# TSOC_Block_Template_Dual_SMD.net
KiCad netlist of a schematic drawn in EAGLE
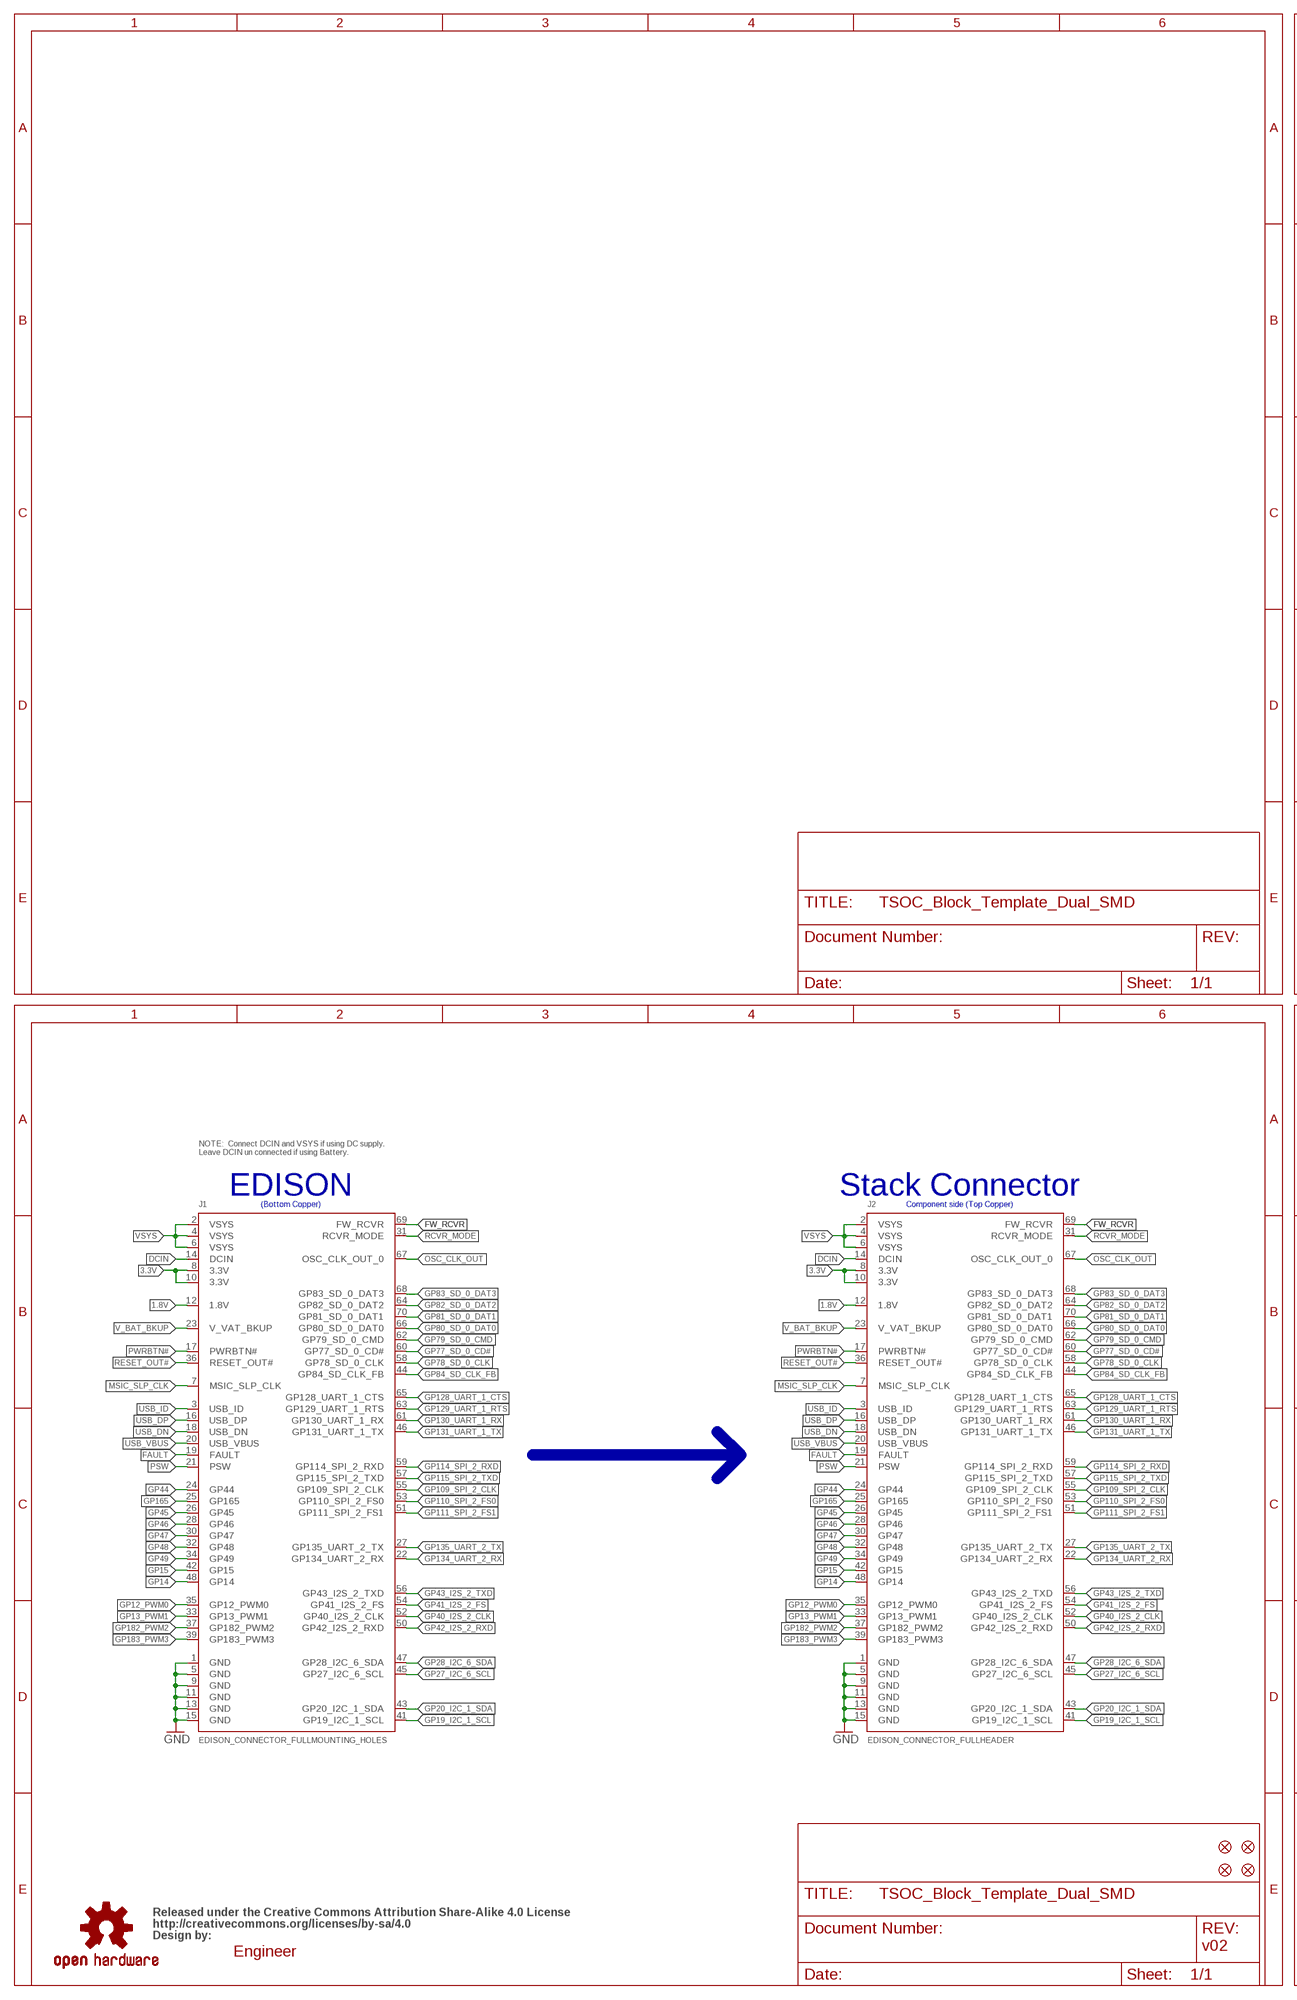
[diagram p0: schematic, sheet 1, part 1 of 2]
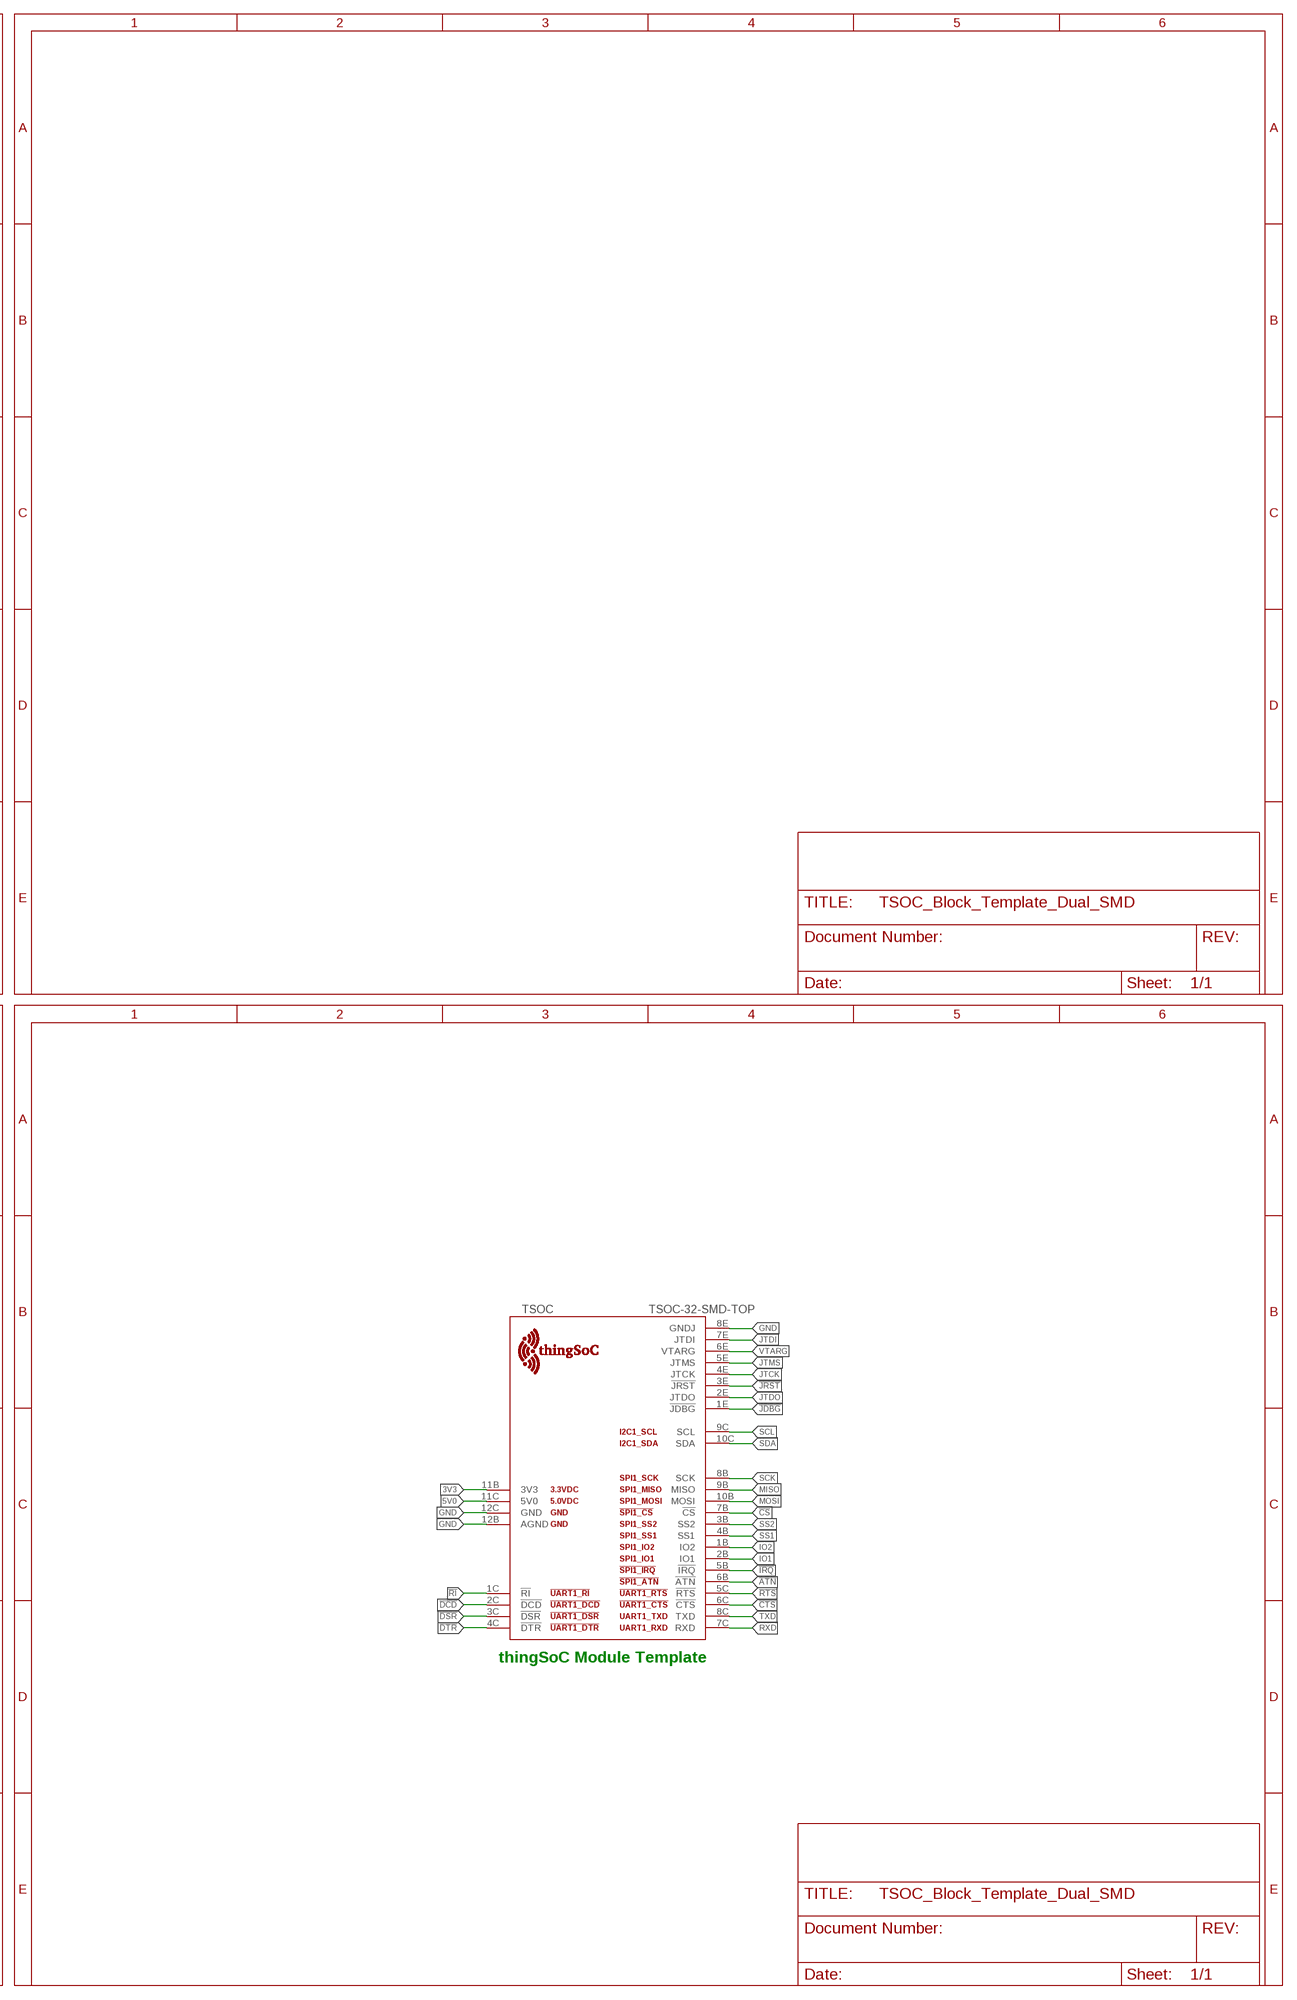
[diagram p1: schematic, sheet 1, part 2 of 2]

(export (version "E")
  (design (tool "Eeschema 10.0.6"))
  (components
    (comp (ref "FID5")
      (value "FIDUCIAL1X2")
      (footprint "eagle-import:FIDUCIAL-1X2")
      (libsource (lib "eagle-import") (part "FIDUCIAL1X2"))
    )
    (comp (ref "FID6")
      (value "FIDUCIAL1X2")
      (footprint "eagle-import:FIDUCIAL-1X2")
      (libsource (lib "eagle-import") (part "FIDUCIAL1X2"))
    )
    (comp (ref "FID7")
      (value "FIDUCIAL1X2")
      (footprint "eagle-import:FIDUCIAL-1X2")
      (libsource (lib "eagle-import") (part "FIDUCIAL1X2"))
    )
    (comp (ref "FID8")
      (value "FIDUCIAL1X2")
      (footprint "eagle-import:FIDUCIAL-1X2")
      (libsource (lib "eagle-import") (part "FIDUCIAL1X2"))
    )
    (comp (ref "J1")
      (value "EDISON_CONNECTOR_FULLMOUNTING_HOLES")
      (footprint "eagle-import:EDISON_DAUGHTER")
      (libsource (lib "eagle-import") (part "EDISON_CONNECTOR_FULLMOUNTING_HOLES"))
    )
    (comp (ref "J2")
      (value "EDISON_CONNECTOR_FULLHEADER")
      (footprint "eagle-import:DF40C-70DP-0.4(51)")
      (libsource (lib "eagle-import") (part "EDISON_CONNECTOR_FULLHEADER"))
    )
    (comp (ref "LOGO5")
      (value "OSHW-LOGOS")
      (footprint "eagle-import:OSHW-LOGO-S")
      (libsource (lib "eagle-import") (part "OSHW-LOGOS"))
    )
    (comp (ref "TSOC")
      (value "TSOC-32-SMD-TOP")
      (footprint "eagle-import:TSOC-BB-S32-SMD-TOP")
      (libsource (lib "eagle-import") (part "TSOC-32-SMD-TOP"))
    )
    (comp (ref "U$1")
      (value "BY_CC_SA_TEXTTEXT")
      (footprint "eagle-import:BY_CC_SA_TEXT")
      (libsource (lib "eagle-import") (part "BY_CC_SA_TEXTTEXT"))
    )
  )
  (nets
    (net (code "1") (name "/~{ATN}") (class "Default")
      (node (ref "TSOC") (pin "6B") (pinfunction "~{ATN}_6B") (pintype "bidirectional"))
    )
    (net (code "2") (name "/~{CS}") (class "Default")
      (node (ref "TSOC") (pin "7B") (pinfunction "~{CS}_7B") (pintype "bidirectional"))
    )
    (net (code "3") (name "/~{CTS}") (class "Default")
      (node (ref "TSOC") (pin "6C") (pinfunction "~{CTS}_6C") (pintype "bidirectional"))
    )
    (net (code "4") (name "/~{DCD}") (class "Default")
      (node (ref "TSOC") (pin "2C") (pinfunction "~{DCD}_2C") (pintype "bidirectional"))
    )
    (net (code "5") (name "/~{DSR}") (class "Default")
      (node (ref "TSOC") (pin "3C") (pinfunction "~{DSR}_3C") (pintype "bidirectional"))
    )
    (net (code "6") (name "/~{DTR}") (class "Default")
      (node (ref "TSOC") (pin "4C") (pinfunction "~{DTR}_4C") (pintype "bidirectional"))
    )
    (net (code "7") (name "/~{IRQ}") (class "Default")
      (node (ref "TSOC") (pin "5B") (pinfunction "~{IRQ}_5B") (pintype "bidirectional"))
    )
    (net (code "8") (name "/~{JDBG}") (class "Default")
      (node (ref "TSOC") (pin "1E") (pinfunction "~{JDBG}_1E") (pintype "bidirectional"))
    )
    (net (code "9") (name "/~{JRST}") (class "Default")
      (node (ref "TSOC") (pin "3E") (pinfunction "~{JRST}_3E") (pintype "bidirectional"))
    )
    (net (code "10") (name "/~{RI}") (class "Default")
      (node (ref "TSOC") (pin "1C") (pinfunction "~{RI}_1C") (pintype "bidirectional"))
    )
    (net (code "11") (name "/~{RTS}") (class "Default")
      (node (ref "TSOC") (pin "5C") (pinfunction "~{RTS}_5C") (pintype "bidirectional"))
    )
    (net (code "12") (name "1.8V") (class "Default")
      (node (ref "J1") (pin "12") (pinfunction "1.8V_12") (pintype "bidirectional"))
      (node (ref "J2") (pin "12") (pinfunction "1.8V_12") (pintype "bidirectional"))
    )
    (net (code "13") (name "3.3V") (class "Default")
      (node (ref "J1") (pin "10") (pinfunction "3.3V_10") (pintype "bidirectional"))
      (node (ref "J1") (pin "8") (pinfunction "3.3V_8") (pintype "bidirectional"))
      (node (ref "J2") (pin "10") (pinfunction "3.3V_10") (pintype "bidirectional"))
      (node (ref "J2") (pin "8") (pinfunction "3.3V_8") (pintype "bidirectional"))
    )
    (net (code "14") (name "3V3") (class "Default")
      (node (ref "TSOC") (pin "11B") (pinfunction "3V3_11B") (pintype "bidirectional"))
    )
    (net (code "15") (name "5V0") (class "Default")
      (node (ref "TSOC") (pin "11C") (pinfunction "5V0_11C") (pintype "bidirectional"))
    )
    (net (code "16") (name "DCIN") (class "Default")
      (node (ref "J1") (pin "14") (pinfunction "DCIN_14") (pintype "bidirectional"))
      (node (ref "J2") (pin "14") (pinfunction "DCIN_14") (pintype "bidirectional"))
    )
    (net (code "17") (name "FAULT") (class "Default")
      (node (ref "J1") (pin "19") (pinfunction "FAULT_19") (pintype "bidirectional"))
      (node (ref "J2") (pin "19") (pinfunction "FAULT_19") (pintype "bidirectional"))
    )
    (net (code "18") (name "FW_RCVR") (class "Default")
      (node (ref "J1") (pin "69") (pinfunction "FW_RCVR_69") (pintype "bidirectional"))
      (node (ref "J2") (pin "69") (pinfunction "FW_RCVR_69") (pintype "bidirectional"))
    )
    (net (code "19") (name "GND") (class "Default")
      (node (ref "J1") (pin "1") (pinfunction "GND_1") (pintype "bidirectional"))
      (node (ref "J1") (pin "11") (pinfunction "GND_11") (pintype "bidirectional"))
      (node (ref "J1") (pin "13") (pinfunction "GND_13") (pintype "bidirectional"))
      (node (ref "J1") (pin "15") (pinfunction "GND_15") (pintype "bidirectional"))
      (node (ref "J1") (pin "5") (pinfunction "GND_5") (pintype "bidirectional"))
      (node (ref "J1") (pin "9") (pinfunction "GND_9") (pintype "bidirectional"))
      (node (ref "J2") (pin "1") (pinfunction "GND_1") (pintype "bidirectional"))
      (node (ref "J2") (pin "11") (pinfunction "GND_11") (pintype "bidirectional"))
      (node (ref "J2") (pin "13") (pinfunction "GND_13") (pintype "bidirectional"))
      (node (ref "J2") (pin "15") (pinfunction "GND_15") (pintype "bidirectional"))
      (node (ref "J2") (pin "5") (pinfunction "GND_5") (pintype "bidirectional"))
      (node (ref "J2") (pin "9") (pinfunction "GND_9") (pintype "bidirectional"))
      (node (ref "TSOC") (pin "12B") (pinfunction "AGND_12B") (pintype "bidirectional"))
      (node (ref "TSOC") (pin "12C") (pinfunction "GND_12C") (pintype "bidirectional"))
      (node (ref "TSOC") (pin "8E") (pinfunction "GNDJ_8E") (pintype "bidirectional"))
    )
    (net (code "20") (name "GP12_PWM0") (class "Default")
      (node (ref "J1") (pin "35") (pinfunction "GP12_PWM0_35") (pintype "bidirectional"))
      (node (ref "J2") (pin "35") (pinfunction "GP12_PWM0_35") (pintype "bidirectional"))
    )
    (net (code "21") (name "GP13_PWM1") (class "Default")
      (node (ref "J1") (pin "33") (pinfunction "GP13_PWM1_33") (pintype "bidirectional"))
      (node (ref "J2") (pin "33") (pinfunction "GP13_PWM1_33") (pintype "bidirectional"))
    )
    (net (code "22") (name "GP14") (class "Default")
      (node (ref "J1") (pin "48") (pinfunction "GP14_48") (pintype "bidirectional"))
      (node (ref "J2") (pin "48") (pinfunction "GP14_48") (pintype "bidirectional"))
    )
    (net (code "23") (name "GP15") (class "Default")
      (node (ref "J1") (pin "42") (pinfunction "GP15_42") (pintype "bidirectional"))
      (node (ref "J2") (pin "42") (pinfunction "GP15_42") (pintype "bidirectional"))
    )
    (net (code "24") (name "GP19_I2C_1_SCL") (class "Default")
      (node (ref "J1") (pin "41") (pinfunction "GP19_I2C_1_SCL_41") (pintype "bidirectional"))
      (node (ref "J2") (pin "41") (pinfunction "GP19_I2C_1_SCL_41") (pintype "bidirectional"))
    )
    (net (code "25") (name "GP20_I2C_1_SDA") (class "Default")
      (node (ref "J1") (pin "43") (pinfunction "GP20_I2C_1_SDA_43") (pintype "bidirectional"))
      (node (ref "J2") (pin "43") (pinfunction "GP20_I2C_1_SDA_43") (pintype "bidirectional"))
    )
    (net (code "26") (name "GP27_I2C_6_SCL") (class "Default")
      (node (ref "J1") (pin "45") (pinfunction "GP27_I2C_6_SCL_45") (pintype "bidirectional"))
      (node (ref "J2") (pin "45") (pinfunction "GP27_I2C_6_SCL_45") (pintype "bidirectional"))
    )
    (net (code "27") (name "GP28_I2C_6_SDA") (class "Default")
      (node (ref "J1") (pin "47") (pinfunction "GP28_I2C_6_SDA_47") (pintype "bidirectional"))
      (node (ref "J2") (pin "47") (pinfunction "GP28_I2C_6_SDA_47") (pintype "bidirectional"))
    )
    (net (code "28") (name "GP40_I2S_2_CLK") (class "Default")
      (node (ref "J1") (pin "52") (pinfunction "GP40_I2S_2_CLK_52") (pintype "bidirectional"))
      (node (ref "J2") (pin "52") (pinfunction "GP40_I2S_2_CLK_52") (pintype "bidirectional"))
    )
    (net (code "29") (name "GP41_I2S_2_FS") (class "Default")
      (node (ref "J1") (pin "54") (pinfunction "GP41_I2S_2_FS_54") (pintype "bidirectional"))
      (node (ref "J2") (pin "54") (pinfunction "GP41_I2S_2_FS_54") (pintype "bidirectional"))
    )
    (net (code "30") (name "GP42_I2S_2_RXD") (class "Default")
      (node (ref "J1") (pin "50") (pinfunction "GP42_I2S_2_RXD_50") (pintype "bidirectional"))
      (node (ref "J2") (pin "50") (pinfunction "GP42_I2S_2_RXD_50") (pintype "bidirectional"))
    )
    (net (code "31") (name "GP43_I2S_2_TXD") (class "Default")
      (node (ref "J1") (pin "56") (pinfunction "GP43_I2S_2_TXD_56") (pintype "bidirectional"))
      (node (ref "J2") (pin "56") (pinfunction "GP43_I2S_2_TXD_56") (pintype "bidirectional"))
    )
    (net (code "32") (name "GP44") (class "Default")
      (node (ref "J1") (pin "24") (pinfunction "GP44_24") (pintype "bidirectional"))
      (node (ref "J2") (pin "24") (pinfunction "GP44_24") (pintype "bidirectional"))
    )
    (net (code "33") (name "GP45") (class "Default")
      (node (ref "J1") (pin "26") (pinfunction "GP45_26") (pintype "bidirectional"))
      (node (ref "J2") (pin "26") (pinfunction "GP45_26") (pintype "bidirectional"))
    )
    (net (code "34") (name "GP46") (class "Default")
      (node (ref "J1") (pin "28") (pinfunction "GP46_28") (pintype "bidirectional"))
      (node (ref "J2") (pin "28") (pinfunction "GP46_28") (pintype "bidirectional"))
    )
    (net (code "35") (name "GP47") (class "Default")
      (node (ref "J1") (pin "30") (pinfunction "GP47_30") (pintype "bidirectional"))
      (node (ref "J2") (pin "30") (pinfunction "GP47_30") (pintype "bidirectional"))
    )
    (net (code "36") (name "GP48") (class "Default")
      (node (ref "J1") (pin "32") (pinfunction "GP48_32") (pintype "bidirectional"))
      (node (ref "J2") (pin "32") (pinfunction "GP48_32") (pintype "bidirectional"))
    )
    (net (code "37") (name "GP49") (class "Default")
      (node (ref "J1") (pin "34") (pinfunction "GP49_34") (pintype "bidirectional"))
      (node (ref "J2") (pin "34") (pinfunction "GP49_34") (pintype "bidirectional"))
    )
    (net (code "38") (name "GP77_SD_0_CD#") (class "Default")
      (node (ref "J1") (pin "60") (pinfunction "GP77_SD_0_CD#_60") (pintype "bidirectional"))
      (node (ref "J2") (pin "60") (pinfunction "GP77_SD_0_CD#_60") (pintype "bidirectional"))
    )
    (net (code "39") (name "GP78_SD_0_CLK") (class "Default")
      (node (ref "J1") (pin "58") (pinfunction "GP78_SD_0_CLK_58") (pintype "bidirectional"))
      (node (ref "J2") (pin "58") (pinfunction "GP78_SD_0_CLK_58") (pintype "bidirectional"))
    )
    (net (code "40") (name "GP79_SD_0_CMD") (class "Default")
      (node (ref "J1") (pin "62") (pinfunction "GP79_SD_0_CMD_62") (pintype "bidirectional"))
      (node (ref "J2") (pin "62") (pinfunction "GP79_SD_0_CMD_62") (pintype "bidirectional"))
    )
    (net (code "41") (name "GP80_SD_0_DAT0") (class "Default")
      (node (ref "J1") (pin "66") (pinfunction "GP80_SD_0_DAT0_66") (pintype "bidirectional"))
      (node (ref "J2") (pin "66") (pinfunction "GP80_SD_0_DAT0_66") (pintype "bidirectional"))
    )
    (net (code "42") (name "GP81_SD_0_DAT1") (class "Default")
      (node (ref "J1") (pin "70") (pinfunction "GP81_SD_0_DAT1_70") (pintype "bidirectional"))
      (node (ref "J2") (pin "70") (pinfunction "GP81_SD_0_DAT1_70") (pintype "bidirectional"))
    )
    (net (code "43") (name "GP82_SD_0_DAT2") (class "Default")
      (node (ref "J1") (pin "64") (pinfunction "GP82_SD_0_DAT2_64") (pintype "bidirectional"))
      (node (ref "J2") (pin "64") (pinfunction "GP82_SD_0_DAT2_64") (pintype "bidirectional"))
    )
    (net (code "44") (name "GP83_SD_0_DAT3") (class "Default")
      (node (ref "J1") (pin "68") (pinfunction "GP83_SD_0_DAT3_68") (pintype "bidirectional"))
      (node (ref "J2") (pin "68") (pinfunction "GP83_SD_0_DAT3_68") (pintype "bidirectional"))
    )
    (net (code "45") (name "GP84_SD_CLK_FB") (class "Default")
      (node (ref "J1") (pin "44") (pinfunction "GP84_SD_CLK_FB_44") (pintype "bidirectional"))
      (node (ref "J2") (pin "44") (pinfunction "GP84_SD_CLK_FB_44") (pintype "bidirectional"))
    )
    (net (code "46") (name "GP109_SPI_2_CLK") (class "Default")
      (node (ref "J1") (pin "55") (pinfunction "GP109_SPI_2_CLK_55") (pintype "bidirectional"))
      (node (ref "J2") (pin "55") (pinfunction "GP109_SPI_2_CLK_55") (pintype "bidirectional"))
    )
    (net (code "47") (name "GP110_SPI_2_FS0") (class "Default")
      (node (ref "J1") (pin "53") (pinfunction "GP110_SPI_2_FS0_53") (pintype "bidirectional"))
      (node (ref "J2") (pin "53") (pinfunction "GP110_SPI_2_FS0_53") (pintype "bidirectional"))
    )
    (net (code "48") (name "GP111_SPI_2_FS1") (class "Default")
      (node (ref "J1") (pin "51") (pinfunction "GP111_SPI_2_FS1_51") (pintype "bidirectional"))
      (node (ref "J2") (pin "51") (pinfunction "GP111_SPI_2_FS1_51") (pintype "bidirectional"))
    )
    (net (code "49") (name "GP114_SPI_2_RXD") (class "Default")
      (node (ref "J1") (pin "59") (pinfunction "GP114_SPI_2_RXD_59") (pintype "bidirectional"))
      (node (ref "J2") (pin "59") (pinfunction "GP114_SPI_2_RXD_59") (pintype "bidirectional"))
    )
    (net (code "50") (name "GP115_SPI_2_TXD") (class "Default")
      (node (ref "J1") (pin "57") (pinfunction "GP115_SPI_2_TXD_57") (pintype "bidirectional"))
      (node (ref "J2") (pin "57") (pinfunction "GP115_SPI_2_TXD_57") (pintype "bidirectional"))
    )
    (net (code "51") (name "GP128_UART_1_CTS") (class "Default")
      (node (ref "J1") (pin "65") (pinfunction "GP128_UART_1_CTS_65") (pintype "bidirectional"))
      (node (ref "J2") (pin "65") (pinfunction "GP128_UART_1_CTS_65") (pintype "bidirectional"))
    )
    (net (code "52") (name "GP129_UART_1_RTS") (class "Default")
      (node (ref "J1") (pin "63") (pinfunction "GP129_UART_1_RTS_63") (pintype "bidirectional"))
      (node (ref "J2") (pin "63") (pinfunction "GP129_UART_1_RTS_63") (pintype "bidirectional"))
    )
    (net (code "53") (name "GP130_UART_1_RX") (class "Default")
      (node (ref "J1") (pin "61") (pinfunction "GP130_UART_1_RX_61") (pintype "bidirectional"))
      (node (ref "J2") (pin "61") (pinfunction "GP130_UART_1_RX_61") (pintype "bidirectional"))
    )
    (net (code "54") (name "GP131_UART_1_TX") (class "Default")
      (node (ref "J1") (pin "46") (pinfunction "GP131_UART_1_TX_46") (pintype "bidirectional"))
      (node (ref "J2") (pin "46") (pinfunction "GP131_UART_1_TX_46") (pintype "bidirectional"))
    )
    (net (code "55") (name "GP134_UART_2_RX") (class "Default")
      (node (ref "J1") (pin "22") (pinfunction "GP134_UART_2_RX_22") (pintype "bidirectional"))
      (node (ref "J2") (pin "22") (pinfunction "GP134_UART_2_RX_22") (pintype "bidirectional"))
    )
    (net (code "56") (name "GP135_UART_2_TX") (class "Default")
      (node (ref "J1") (pin "27") (pinfunction "GP135_UART_2_TX_27") (pintype "bidirectional"))
      (node (ref "J2") (pin "27") (pinfunction "GP135_UART_2_TX_27") (pintype "bidirectional"))
    )
    (net (code "57") (name "GP165") (class "Default")
      (node (ref "J1") (pin "25") (pinfunction "GP165_25") (pintype "bidirectional"))
      (node (ref "J2") (pin "25") (pinfunction "GP165_25") (pintype "bidirectional"))
    )
    (net (code "58") (name "GP182_PWM2") (class "Default")
      (node (ref "J1") (pin "37") (pinfunction "GP182_PWM2_37") (pintype "bidirectional"))
      (node (ref "J2") (pin "37") (pinfunction "GP182_PWM2_37") (pintype "bidirectional"))
    )
    (net (code "59") (name "GP183_PWM3") (class "Default")
      (node (ref "J1") (pin "39") (pinfunction "GP183_PWM3_39") (pintype "bidirectional"))
      (node (ref "J2") (pin "39") (pinfunction "GP183_PWM3_39") (pintype "bidirectional"))
    )
    (net (code "60") (name "IO1") (class "Default")
      (node (ref "TSOC") (pin "2B") (pinfunction "IO1_2B") (pintype "bidirectional"))
    )
    (net (code "61") (name "IO2") (class "Default")
      (node (ref "TSOC") (pin "1B") (pinfunction "IO2_1B") (pintype "bidirectional"))
    )
    (net (code "62") (name "JTCK") (class "Default")
      (node (ref "TSOC") (pin "4E") (pinfunction "JTCK_4E") (pintype "bidirectional"))
    )
    (net (code "63") (name "JTDI") (class "Default")
      (node (ref "TSOC") (pin "7E") (pinfunction "JTDI_7E") (pintype "bidirectional"))
    )
    (net (code "64") (name "JTDO") (class "Default")
      (node (ref "TSOC") (pin "2E") (pinfunction "JTDO_2E") (pintype "bidirectional"))
    )
    (net (code "65") (name "JTMS") (class "Default")
      (node (ref "TSOC") (pin "5E") (pinfunction "JTMS_5E") (pintype "bidirectional"))
    )
    (net (code "66") (name "MISO") (class "Default")
      (node (ref "TSOC") (pin "9B") (pinfunction "MISO_9B") (pintype "bidirectional"))
    )
    (net (code "67") (name "MOSI") (class "Default")
      (node (ref "TSOC") (pin "10B") (pinfunction "MOSI_10B") (pintype "bidirectional"))
    )
    (net (code "68") (name "MSIC_SLP_CLK") (class "Default")
      (node (ref "J1") (pin "7") (pinfunction "MSIC_SLP_CLK_7") (pintype "bidirectional"))
      (node (ref "J2") (pin "7") (pinfunction "MSIC_SLP_CLK_7") (pintype "bidirectional"))
    )
    (net (code "69") (name "OSC_CLK_OUT") (class "Default")
      (node (ref "J1") (pin "67") (pinfunction "OSC_CLK_OUT_0_67") (pintype "bidirectional"))
      (node (ref "J2") (pin "67") (pinfunction "OSC_CLK_OUT_0_67") (pintype "bidirectional"))
    )
    (net (code "70") (name "PSW") (class "Default")
      (node (ref "J1") (pin "21") (pinfunction "PSW_21") (pintype "bidirectional"))
      (node (ref "J2") (pin "21") (pinfunction "PSW_21") (pintype "bidirectional"))
    )
    (net (code "71") (name "PWRBTN#") (class "Default")
      (node (ref "J1") (pin "17") (pinfunction "PWRBTN#_17") (pintype "bidirectional"))
      (node (ref "J2") (pin "17") (pinfunction "PWRBTN#_17") (pintype "bidirectional"))
    )
    (net (code "72") (name "RCVR_MODE") (class "Default")
      (node (ref "J1") (pin "31") (pinfunction "RCVR_MODE_31") (pintype "bidirectional"))
      (node (ref "J2") (pin "31") (pinfunction "RCVR_MODE_31") (pintype "bidirectional"))
    )
    (net (code "73") (name "RESET_OUT#") (class "Default")
      (node (ref "J1") (pin "36") (pinfunction "RESET_OUT#_36") (pintype "bidirectional"))
      (node (ref "J2") (pin "36") (pinfunction "RESET_OUT#_36") (pintype "bidirectional"))
    )
    (net (code "74") (name "RXD") (class "Default")
      (node (ref "TSOC") (pin "7C") (pinfunction "RXD_7C") (pintype "bidirectional"))
    )
    (net (code "75") (name "SCK") (class "Default")
      (node (ref "TSOC") (pin "8B") (pinfunction "SCK_8B") (pintype "bidirectional"))
    )
    (net (code "76") (name "SCL") (class "Default")
      (node (ref "TSOC") (pin "9C") (pinfunction "SCL_9C") (pintype "bidirectional"))
    )
    (net (code "77") (name "SDA") (class "Default")
      (node (ref "TSOC") (pin "10C") (pinfunction "SDA_10C") (pintype "bidirectional"))
    )
    (net (code "78") (name "SS1") (class "Default")
      (node (ref "TSOC") (pin "4B") (pinfunction "SS1_4B") (pintype "bidirectional"))
    )
    (net (code "79") (name "SS2") (class "Default")
      (node (ref "TSOC") (pin "3B") (pinfunction "SS2_3B") (pintype "bidirectional"))
    )
    (net (code "80") (name "TXD") (class "Default")
      (node (ref "TSOC") (pin "8C") (pinfunction "TXD_8C") (pintype "bidirectional"))
    )
    (net (code "81") (name "USB_DN") (class "Default")
      (node (ref "J1") (pin "18") (pinfunction "USB_DN_18") (pintype "bidirectional"))
      (node (ref "J2") (pin "18") (pinfunction "USB_DN_18") (pintype "bidirectional"))
    )
    (net (code "82") (name "USB_DP") (class "Default")
      (node (ref "J1") (pin "16") (pinfunction "USB_DP_16") (pintype "bidirectional"))
      (node (ref "J2") (pin "16") (pinfunction "USB_DP_16") (pintype "bidirectional"))
    )
    (net (code "83") (name "USB_ID") (class "Default")
      (node (ref "J1") (pin "3") (pinfunction "USB_ID_3") (pintype "bidirectional"))
      (node (ref "J2") (pin "3") (pinfunction "USB_ID_3") (pintype "bidirectional"))
    )
    (net (code "84") (name "USB_VBUS") (class "Default")
      (node (ref "J1") (pin "20") (pinfunction "USB_VBUS_20") (pintype "bidirectional"))
      (node (ref "J2") (pin "20") (pinfunction "USB_VBUS_20") (pintype "bidirectional"))
    )
    (net (code "85") (name "VSYS") (class "Default")
      (node (ref "J1") (pin "2") (pinfunction "VSYS_2") (pintype "bidirectional"))
      (node (ref "J1") (pin "4") (pinfunction "VSYS_4") (pintype "bidirectional"))
      (node (ref "J1") (pin "6") (pinfunction "VSYS_6") (pintype "bidirectional"))
      (node (ref "J2") (pin "2") (pinfunction "VSYS_2") (pintype "bidirectional"))
      (node (ref "J2") (pin "4") (pinfunction "VSYS_4") (pintype "bidirectional"))
      (node (ref "J2") (pin "6") (pinfunction "VSYS_6") (pintype "bidirectional"))
    )
    (net (code "86") (name "VTARG") (class "Default")
      (node (ref "TSOC") (pin "6E") (pinfunction "VTARG_6E") (pintype "bidirectional"))
    )
    (net (code "87") (name "V_BAT_BKUP") (class "Default")
      (node (ref "J1") (pin "23") (pinfunction "V_VAT_BKUP_23") (pintype "bidirectional"))
      (node (ref "J2") (pin "23") (pinfunction "V_VAT_BKUP_23") (pintype "bidirectional"))
    )
  )
)
